# usb64.net
KiCad netlist of a schematic drawn in EAGLE
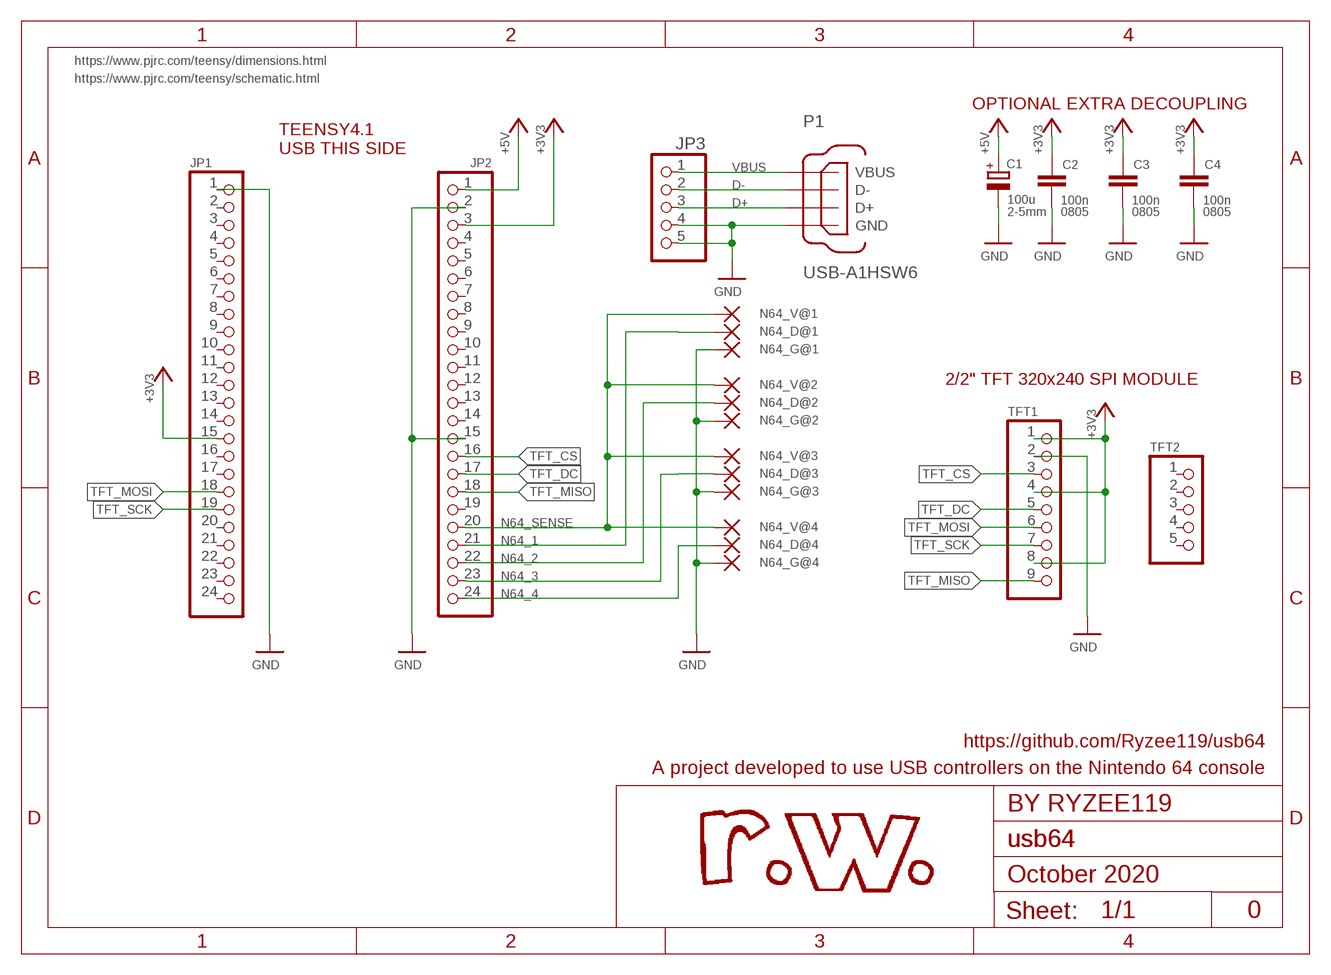
[diagram p0: schematic, sheet 1]

(export (version "E")
  (design (tool "Eeschema 10.0.6"))
  (components
    (comp (ref "C1")
      (value "100u")
      (footprint "eagle-import:E2-5")
      (libsource (lib "eagle-import") (part "CPOL-EUE2-5"))
    )
    (comp (ref "C2")
      (value "100n")
      (footprint "eagle-import:C0805K")
      (libsource (lib "eagle-import") (part "C-EUC0805K"))
    )
    (comp (ref "C3")
      (value "100n")
      (footprint "eagle-import:C0805K")
      (libsource (lib "eagle-import") (part "C-EUC0805K"))
    )
    (comp (ref "C4")
      (value "100n")
      (footprint "eagle-import:C0805K")
      (libsource (lib "eagle-import") (part "C-EUC0805K"))
    )
    (comp (ref "JP1")
      (value "PINHD-1X24")
      (footprint "eagle-import:1X24")
      (libsource (lib "eagle-import") (part "PINHD-1X24"))
    )
    (comp (ref "JP2")
      (value "PINHD-1X24")
      (footprint "eagle-import:1X24")
      (libsource (lib "eagle-import") (part "PINHD-1X24"))
    )
    (comp (ref "JP3")
      (value "PINHD-1X5")
      (footprint "eagle-import:1X05")
      (libsource (lib "eagle-import") (part "PINHD-1X5"))
    )
    (comp (ref "N64_D@1")
      (value "SMD2")
      (footprint "eagle-import:SMD1,27-2,54")
      (libsource (lib "eagle-import") (part "SMD2"))
    )
    (comp (ref "N64_D@2")
      (value "SMD2")
      (footprint "eagle-import:SMD1,27-2,54")
      (libsource (lib "eagle-import") (part "SMD2"))
    )
    (comp (ref "N64_D@3")
      (value "SMD2")
      (footprint "eagle-import:SMD1,27-2,54")
      (libsource (lib "eagle-import") (part "SMD2"))
    )
    (comp (ref "N64_D@4")
      (value "SMD2")
      (footprint "eagle-import:SMD1,27-2,54")
      (libsource (lib "eagle-import") (part "SMD2"))
    )
    (comp (ref "N64_G@1")
      (value "SMD2")
      (footprint "eagle-import:SMD1,27-2,54")
      (libsource (lib "eagle-import") (part "SMD2"))
    )
    (comp (ref "N64_G@2")
      (value "SMD2")
      (footprint "eagle-import:SMD1,27-2,54")
      (libsource (lib "eagle-import") (part "SMD2"))
    )
    (comp (ref "N64_G@3")
      (value "SMD2")
      (footprint "eagle-import:SMD1,27-2,54")
      (libsource (lib "eagle-import") (part "SMD2"))
    )
    (comp (ref "N64_G@4")
      (value "SMD2")
      (footprint "eagle-import:SMD1,27-2,54")
      (libsource (lib "eagle-import") (part "SMD2"))
    )
    (comp (ref "N64_V@1")
      (value "SMD2")
      (footprint "eagle-import:SMD1,27-2,54")
      (libsource (lib "eagle-import") (part "SMD2"))
    )
    (comp (ref "N64_V@2")
      (value "SMD2")
      (footprint "eagle-import:SMD1,27-2,54")
      (libsource (lib "eagle-import") (part "SMD2"))
    )
    (comp (ref "N64_V@3")
      (value "SMD2")
      (footprint "eagle-import:SMD1,27-2,54")
      (libsource (lib "eagle-import") (part "SMD2"))
    )
    (comp (ref "N64_V@4")
      (value "SMD2")
      (footprint "eagle-import:SMD1,27-2,54")
      (libsource (lib "eagle-import") (part "SMD2"))
    )
    (comp (ref "P1")
      (value "USB-A1HSW6")
      (footprint "eagle-import:OST_USB-A1HSW6")
      (fields (field (name "DIGI-KEY_PART_NUMBER") "ED2989-ND") (field (name "MF") "On Shore"))
      (libsource (lib "eagle-import") (part "USB-A1HSW6"))
    )
    (comp (ref "TFT1")
      (value "PINHD-1X9")
      (footprint "eagle-import:1X09")
      (libsource (lib "eagle-import") (part "PINHD-1X9"))
    )
    (comp (ref "TFT2")
      (value "PINHD-1X5")
      (footprint "eagle-import:1X05")
      (libsource (lib "eagle-import") (part "PINHD-1X5"))
    )
  )
  (nets
    (net (code "1") (name "+3V3") (class "Default")
      (node (ref "C2") (pin "1") (pinfunction "1_1") (pintype "passive"))
      (node (ref "C3") (pin "1") (pinfunction "1_1") (pintype "passive"))
      (node (ref "C4") (pin "1") (pinfunction "1_1") (pintype "passive"))
      (node (ref "JP1") (pin "15") (pinfunction "15_15") (pintype "passive"))
      (node (ref "JP2") (pin "3") (pinfunction "3_3") (pintype "passive"))
      (node (ref "TFT1") (pin "1") (pinfunction "1_1") (pintype "passive"))
      (node (ref "TFT1") (pin "4") (pinfunction "4_4") (pintype "passive"))
      (node (ref "TFT1") (pin "8") (pinfunction "8_8") (pintype "passive"))
    )
    (net (code "2") (name "+5V") (class "Default")
      (node (ref "C1") (pin "+") (pinfunction "+_+") (pintype "passive"))
      (node (ref "JP2") (pin "1") (pinfunction "1_1") (pintype "passive"))
    )
    (net (code "3") (name "/D+") (class "Default")
      (node (ref "JP3") (pin "3") (pinfunction "3_3") (pintype "passive"))
      (node (ref "P1") (pin "3") (pinfunction "D+_3") (pintype "bidirectional"))
    )
    (net (code "4") (name "/D-") (class "Default")
      (node (ref "JP3") (pin "2") (pinfunction "2_2") (pintype "passive"))
      (node (ref "P1") (pin "2") (pinfunction "D-_2") (pintype "bidirectional"))
    )
    (net (code "5") (name "/N64_1") (class "Default")
      (node (ref "JP2") (pin "21") (pinfunction "21_21") (pintype "passive"))
      (node (ref "N64_D@1") (pin "1") (pinfunction "P_1") (pintype "passive"))
    )
    (net (code "6") (name "/N64_2") (class "Default")
      (node (ref "JP2") (pin "22") (pinfunction "22_22") (pintype "passive"))
      (node (ref "N64_D@2") (pin "1") (pinfunction "P_1") (pintype "passive"))
    )
    (net (code "7") (name "/N64_3") (class "Default")
      (node (ref "JP2") (pin "23") (pinfunction "23_23") (pintype "passive"))
      (node (ref "N64_D@3") (pin "1") (pinfunction "P_1") (pintype "passive"))
    )
    (net (code "8") (name "/N64_4") (class "Default")
      (node (ref "JP2") (pin "24") (pinfunction "24_24") (pintype "passive"))
      (node (ref "N64_D@4") (pin "1") (pinfunction "P_1") (pintype "passive"))
    )
    (net (code "9") (name "/N64_SENSE") (class "Default")
      (node (ref "JP2") (pin "20") (pinfunction "20_20") (pintype "passive"))
      (node (ref "N64_V@1") (pin "1") (pinfunction "P_1") (pintype "passive"))
      (node (ref "N64_V@2") (pin "1") (pinfunction "P_1") (pintype "passive"))
      (node (ref "N64_V@3") (pin "1") (pinfunction "P_1") (pintype "passive"))
      (node (ref "N64_V@4") (pin "1") (pinfunction "P_1") (pintype "passive"))
    )
    (net (code "10") (name "/VBUS") (class "Default")
      (node (ref "JP3") (pin "1") (pinfunction "1_1") (pintype "passive"))
      (node (ref "P1") (pin "1") (pinfunction "VBUS_1") (pintype "power_in"))
    )
    (net (code "11") (name "GND") (class "Default")
      (node (ref "C1") (pin "-") (pinfunction "-_-") (pintype "passive"))
      (node (ref "C2") (pin "2") (pinfunction "2_2") (pintype "passive"))
      (node (ref "C3") (pin "2") (pinfunction "2_2") (pintype "passive"))
      (node (ref "C4") (pin "2") (pinfunction "2_2") (pintype "passive"))
      (node (ref "JP1") (pin "1") (pinfunction "1_1") (pintype "passive"))
      (node (ref "JP2") (pin "15") (pinfunction "15_15") (pintype "passive"))
      (node (ref "JP2") (pin "2") (pinfunction "2_2") (pintype "passive"))
      (node (ref "JP3") (pin "4") (pinfunction "4_4") (pintype "passive"))
      (node (ref "JP3") (pin "5") (pinfunction "5_5") (pintype "passive"))
      (node (ref "N64_G@1") (pin "1") (pinfunction "P_1") (pintype "passive"))
      (node (ref "N64_G@2") (pin "1") (pinfunction "P_1") (pintype "passive"))
      (node (ref "N64_G@3") (pin "1") (pinfunction "P_1") (pintype "passive"))
      (node (ref "N64_G@4") (pin "1") (pinfunction "P_1") (pintype "passive"))
      (node (ref "P1") (pin "4") (pinfunction "GND_4") (pintype "power_in"))
      (node (ref "TFT1") (pin "2") (pinfunction "2_2") (pintype "passive"))
    )
    (net (code "12") (name "TFT_CS") (class "Default")
      (node (ref "JP2") (pin "16") (pinfunction "16_16") (pintype "passive"))
      (node (ref "TFT1") (pin "3") (pinfunction "3_3") (pintype "passive"))
    )
    (net (code "13") (name "TFT_DC") (class "Default")
      (node (ref "JP2") (pin "17") (pinfunction "17_17") (pintype "passive"))
      (node (ref "TFT1") (pin "5") (pinfunction "5_5") (pintype "passive"))
    )
    (net (code "14") (name "TFT_MISO") (class "Default")
      (node (ref "JP2") (pin "18") (pinfunction "18_18") (pintype "passive"))
      (node (ref "TFT1") (pin "9") (pinfunction "9_9") (pintype "passive"))
    )
    (net (code "15") (name "TFT_MOSI") (class "Default")
      (node (ref "JP1") (pin "18") (pinfunction "18_18") (pintype "passive"))
      (node (ref "TFT1") (pin "6") (pinfunction "6_6") (pintype "passive"))
    )
    (net (code "16") (name "TFT_SCK") (class "Default")
      (node (ref "JP1") (pin "19") (pinfunction "19_19") (pintype "passive"))
      (node (ref "TFT1") (pin "7") (pinfunction "7_7") (pintype "passive"))
    )
    (net (code "17") (name "unconnected-(JP1-Pad2)") (class "Default")
      (node (ref "JP1") (pin "2") (pinfunction "2_2") (pintype "passive"))
    )
    (net (code "18") (name "unconnected-(JP1-Pad3)") (class "Default")
      (node (ref "JP1") (pin "3") (pinfunction "3_3") (pintype "passive"))
    )
    (net (code "19") (name "unconnected-(JP1-Pad4)") (class "Default")
      (node (ref "JP1") (pin "4") (pinfunction "4_4") (pintype "passive"))
    )
    (net (code "20") (name "unconnected-(JP1-Pad5)") (class "Default")
      (node (ref "JP1") (pin "5") (pinfunction "5_5") (pintype "passive"))
    )
    (net (code "21") (name "unconnected-(JP1-Pad6)") (class "Default")
      (node (ref "JP1") (pin "6") (pinfunction "6_6") (pintype "passive"))
    )
    (net (code "22") (name "unconnected-(JP1-Pad7)") (class "Default")
      (node (ref "JP1") (pin "7") (pinfunction "7_7") (pintype "passive"))
    )
    (net (code "23") (name "unconnected-(JP1-Pad8)") (class "Default")
      (node (ref "JP1") (pin "8") (pinfunction "8_8") (pintype "passive"))
    )
    (net (code "24") (name "unconnected-(JP1-Pad9)") (class "Default")
      (node (ref "JP1") (pin "9") (pinfunction "9_9") (pintype "passive"))
    )
    (net (code "25") (name "unconnected-(JP1-Pad10)") (class "Default")
      (node (ref "JP1") (pin "10") (pinfunction "10_10") (pintype "passive"))
    )
    (net (code "26") (name "unconnected-(JP1-Pad11)") (class "Default")
      (node (ref "JP1") (pin "11") (pinfunction "11_11") (pintype "passive"))
    )
    (net (code "27") (name "unconnected-(JP1-Pad12)") (class "Default")
      (node (ref "JP1") (pin "12") (pinfunction "12_12") (pintype "passive"))
    )
    (net (code "28") (name "unconnected-(JP1-Pad13)") (class "Default")
      (node (ref "JP1") (pin "13") (pinfunction "13_13") (pintype "passive"))
    )
    (net (code "29") (name "unconnected-(JP1-Pad14)") (class "Default")
      (node (ref "JP1") (pin "14") (pinfunction "14_14") (pintype "passive"))
    )
    (net (code "30") (name "unconnected-(JP1-Pad16)") (class "Default")
      (node (ref "JP1") (pin "16") (pinfunction "16_16") (pintype "passive"))
    )
    (net (code "31") (name "unconnected-(JP1-Pad17)") (class "Default")
      (node (ref "JP1") (pin "17") (pinfunction "17_17") (pintype "passive"))
    )
    (net (code "32") (name "unconnected-(JP1-Pad20)") (class "Default")
      (node (ref "JP1") (pin "20") (pinfunction "20_20") (pintype "passive"))
    )
    (net (code "33") (name "unconnected-(JP1-Pad21)") (class "Default")
      (node (ref "JP1") (pin "21") (pinfunction "21_21") (pintype "passive"))
    )
    (net (code "34") (name "unconnected-(JP1-Pad22)") (class "Default")
      (node (ref "JP1") (pin "22") (pinfunction "22_22") (pintype "passive"))
    )
    (net (code "35") (name "unconnected-(JP1-Pad23)") (class "Default")
      (node (ref "JP1") (pin "23") (pinfunction "23_23") (pintype "passive"))
    )
    (net (code "36") (name "unconnected-(JP1-Pad24)") (class "Default")
      (node (ref "JP1") (pin "24") (pinfunction "24_24") (pintype "passive"))
    )
    (net (code "37") (name "unconnected-(JP2-Pad4)") (class "Default")
      (node (ref "JP2") (pin "4") (pinfunction "4_4") (pintype "passive"))
    )
    (net (code "38") (name "unconnected-(JP2-Pad5)") (class "Default")
      (node (ref "JP2") (pin "5") (pinfunction "5_5") (pintype "passive"))
    )
    (net (code "39") (name "unconnected-(JP2-Pad6)") (class "Default")
      (node (ref "JP2") (pin "6") (pinfunction "6_6") (pintype "passive"))
    )
    (net (code "40") (name "unconnected-(JP2-Pad7)") (class "Default")
      (node (ref "JP2") (pin "7") (pinfunction "7_7") (pintype "passive"))
    )
    (net (code "41") (name "unconnected-(JP2-Pad8)") (class "Default")
      (node (ref "JP2") (pin "8") (pinfunction "8_8") (pintype "passive"))
    )
    (net (code "42") (name "unconnected-(JP2-Pad9)") (class "Default")
      (node (ref "JP2") (pin "9") (pinfunction "9_9") (pintype "passive"))
    )
    (net (code "43") (name "unconnected-(JP2-Pad10)") (class "Default")
      (node (ref "JP2") (pin "10") (pinfunction "10_10") (pintype "passive"))
    )
    (net (code "44") (name "unconnected-(JP2-Pad11)") (class "Default")
      (node (ref "JP2") (pin "11") (pinfunction "11_11") (pintype "passive"))
    )
    (net (code "45") (name "unconnected-(JP2-Pad12)") (class "Default")
      (node (ref "JP2") (pin "12") (pinfunction "12_12") (pintype "passive"))
    )
    (net (code "46") (name "unconnected-(JP2-Pad13)") (class "Default")
      (node (ref "JP2") (pin "13") (pinfunction "13_13") (pintype "passive"))
    )
    (net (code "47") (name "unconnected-(JP2-Pad14)") (class "Default")
      (node (ref "JP2") (pin "14") (pinfunction "14_14") (pintype "passive"))
    )
    (net (code "48") (name "unconnected-(JP2-Pad19)") (class "Default")
      (node (ref "JP2") (pin "19") (pinfunction "19_19") (pintype "passive"))
    )
    (net (code "49") (name "unconnected-(TFT2-Pad1)") (class "Default")
      (node (ref "TFT2") (pin "1") (pinfunction "1_1") (pintype "passive"))
    )
    (net (code "50") (name "unconnected-(TFT2-Pad2)") (class "Default")
      (node (ref "TFT2") (pin "2") (pinfunction "2_2") (pintype "passive"))
    )
    (net (code "51") (name "unconnected-(TFT2-Pad3)") (class "Default")
      (node (ref "TFT2") (pin "3") (pinfunction "3_3") (pintype "passive"))
    )
    (net (code "52") (name "unconnected-(TFT2-Pad4)") (class "Default")
      (node (ref "TFT2") (pin "4") (pinfunction "4_4") (pintype "passive"))
    )
    (net (code "53") (name "unconnected-(TFT2-Pad5)") (class "Default")
      (node (ref "TFT2") (pin "5") (pinfunction "5_5") (pintype "passive"))
    )
  )
)
